# Power.net
KiCad netlist of a schematic drawn in Altium Designer
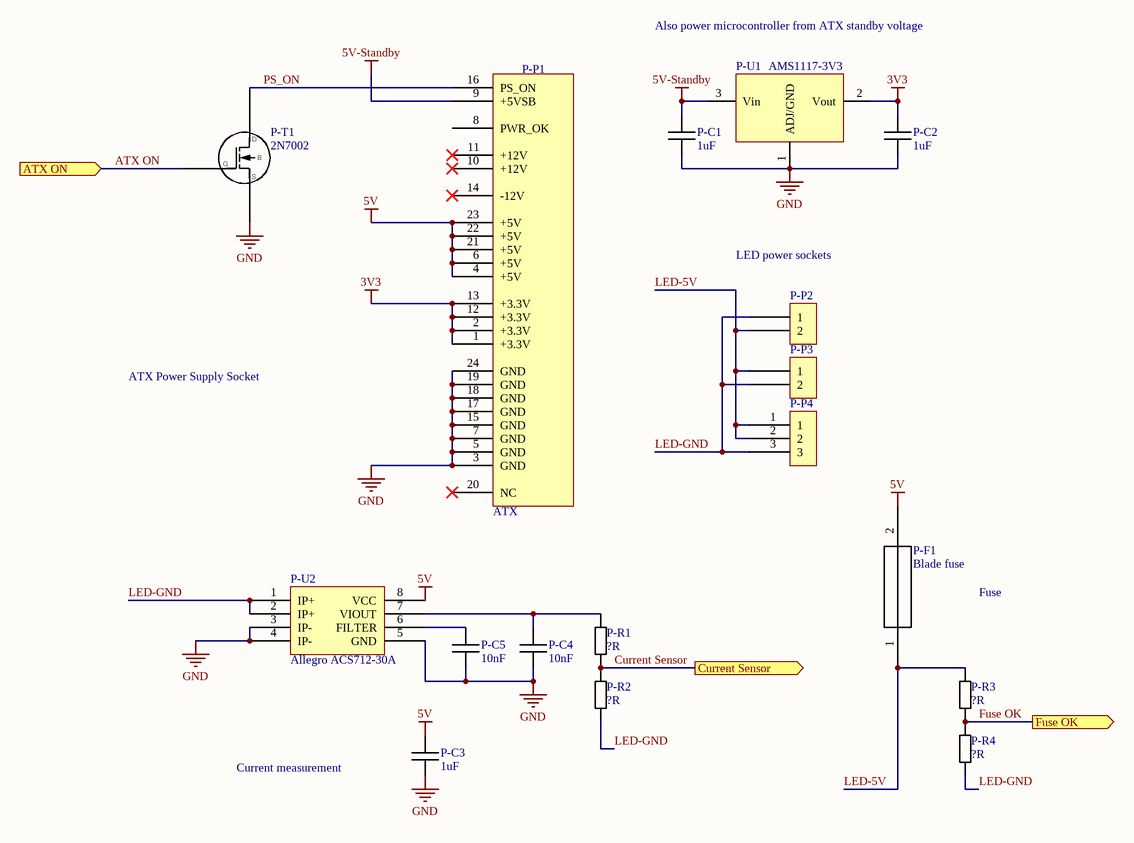
[diagram p0: Power.SchDoc]

(export (version "E")
  (design (tool "Eeschema 10.0.6"))
  (components
    (comp (ref "P-C1")
      (value "1uF")
      (footprint "C 0805 / 2012")
      (libsource (lib "Standard") (part "Capacitor"))
    )
    (comp (ref "P-C2")
      (value "1uF")
      (footprint "C 0805 / 2012")
      (libsource (lib "Standard") (part "Capacitor"))
    )
    (comp (ref "P-C3")
      (value "1uF")
      (footprint "C 0805 / 2012")
      (libsource (lib "Standard") (part "Capacitor"))
    )
    (comp (ref "P-C4")
      (value "10nF")
      (footprint "R 0805 / 2012 wide")
      (libsource (lib "Standard") (part "Capacitor"))
    )
    (comp (ref "P-C5")
      (value "10nF")
      (footprint "C 0805 / 2012")
      (libsource (lib "Standard") (part "Capacitor"))
    )
    (comp (ref "P-F1")
      (value "Blade fuse")
      (footprint "Blade fuse receptacle")
      (libsource (lib "Standard") (part "Fuse"))
    )
    (comp (ref "P-P1") (value "ATX") (footprint "ATX") (libsource (lib "Connectors") (part "ATX sorted")))
    (comp (ref "P-P2")
      (value "Header 2x1")
      (footprint "Screw terminal 2 pin RM 5mm")
      (libsource (lib "Headers") (part "Header 2x1"))
    )
    (comp (ref "P-P3")
      (value "Header 2x1")
      (footprint "Screw terminal 2 pin RM 5mm")
      (libsource (lib "Headers") (part "Header 2x1"))
    )
    (comp (ref "P-P4")
      (value "Header 1x3")
      (footprint "Screw terminal 3 pin RM 7.62mm")
      (libsource (lib "Headers") (part "Header 1x3"))
    )
    (comp (ref "P-R1")
      (value "?R")
      (footprint "R 0805 / 2012")
      (libsource (lib "Standard") (part "Resistor"))
    )
    (comp (ref "P-R2")
      (value "?R")
      (footprint "R 0805 / 2012")
      (libsource (lib "Standard") (part "Resistor"))
    )
    (comp (ref "P-R3")
      (value "?R")
      (footprint "R 0805 / 2012")
      (libsource (lib "Standard") (part "Resistor"))
    )
    (comp (ref "P-R4")
      (value "?R")
      (footprint "R 0805 / 2012")
      (libsource (lib "Standard") (part "Resistor"))
    )
    (comp (ref "P-T1")
      (value "2N7002")
      (footprint "SOT-23-3")
      (description "N-FET")
      (libsource (lib "ICs") (part "2N7002"))
    )
    (comp (ref "P-U1")
      (value "AMS1117-3V3")
      (footprint "SOT-223-3")
      (description "LDO 3.3V/5V/12V")
      (libsource (lib "ICs") (part "AMS1117"))
    )
    (comp (ref "P-U2")
      (value "Allegro ACS712-30A")
      (footprint "SOIC-8")
      (description "Analog current sensor")
      (libsource (lib "ICs") (part "Allegro ACS712"))
    )
  )
  (nets
    (net (code "1") (name "/ATX ON") (class "Default")
      (node (ref "P-T1") (pin "1") (pinfunction "1_1") (pintype "passive"))
    )
    (net (code "2") (name "/Current Sensor") (class "Default")
      (node (ref "P-R1") (pin "1") (pinfunction "1_1") (pintype "passive"))
      (node (ref "P-R2") (pin "2") (pinfunction "2_2") (pintype "passive"))
    )
    (net (code "3") (name "/Fuse OK") (class "Default")
      (node (ref "P-R3") (pin "1") (pinfunction "1_1") (pintype "passive"))
      (node (ref "P-R4") (pin "2") (pinfunction "2_2") (pintype "passive"))
    )
    (net (code "4") (name "/LED-5V") (class "Default")
      (node (ref "P-F1") (pin "1") (pinfunction "1_1") (pintype "passive"))
      (node (ref "P-P2") (pin "2") (pinfunction "2_2") (pintype "passive"))
      (node (ref "P-P3") (pin "1") (pinfunction "1_1") (pintype "passive"))
      (node (ref "P-P4") (pin "1") (pinfunction "1_1") (pintype "passive"))
      (node (ref "P-P4") (pin "2") (pinfunction "2_2") (pintype "passive"))
      (node (ref "P-R3") (pin "2") (pinfunction "2_2") (pintype "passive"))
    )
    (net (code "5") (name "/LED-GND") (class "Default")
      (node (ref "P-P2") (pin "1") (pinfunction "1_1") (pintype "passive"))
      (node (ref "P-P3") (pin "2") (pinfunction "2_2") (pintype "passive"))
      (node (ref "P-P4") (pin "3") (pinfunction "3_3") (pintype "passive"))
      (node (ref "P-R2") (pin "1") (pinfunction "1_1") (pintype "passive"))
      (node (ref "P-R4") (pin "1") (pinfunction "1_1") (pintype "passive"))
      (node (ref "P-U2") (pin "1") (pinfunction "IP+_1") (pintype "passive"))
      (node (ref "P-U2") (pin "2") (pinfunction "IP+_2") (pintype "passive"))
    )
    (net (code "6") (name "/PS_ON") (class "Default")
      (node (ref "P-P1") (pin "16") (pinfunction "PS_ON_16") (pintype "passive"))
      (node (ref "P-T1") (pin "3") (pinfunction "3_3") (pintype "passive"))
    )
    (net (code "7") (name "3V3") (class "Default")
      (node (ref "P-C2") (pin "1") (pinfunction "1_1") (pintype "passive"))
      (node (ref "P-P1") (pin "1") (pinfunction "+3.3V_1") (pintype "passive"))
      (node (ref "P-P1") (pin "12") (pinfunction "+3.3V_12") (pintype "passive"))
      (node (ref "P-P1") (pin "13") (pinfunction "+3.3V_13") (pintype "passive"))
      (node (ref "P-P1") (pin "2") (pinfunction "+3.3V_2") (pintype "passive"))
      (node (ref "P-U1") (pin "2") (pinfunction "Vout_2") (pintype "passive"))
    )
    (net (code "8") (name "5V") (class "Default")
      (node (ref "P-C3") (pin "1") (pinfunction "1_1") (pintype "passive"))
      (node (ref "P-F1") (pin "2") (pinfunction "2_2") (pintype "passive"))
      (node (ref "P-P1") (pin "21") (pinfunction "+5V_21") (pintype "passive"))
      (node (ref "P-P1") (pin "22") (pinfunction "+5V_22") (pintype "passive"))
      (node (ref "P-P1") (pin "23") (pinfunction "+5V_23") (pintype "passive"))
      (node (ref "P-P1") (pin "4") (pinfunction "+5V_4") (pintype "passive"))
      (node (ref "P-P1") (pin "6") (pinfunction "+5V_6") (pintype "passive"))
      (node (ref "P-U2") (pin "8") (pinfunction "VCC_8") (pintype "passive"))
    )
    (net (code "9") (name "5V-Standby") (class "Default")
      (node (ref "P-C1") (pin "1") (pinfunction "1_1") (pintype "passive"))
      (node (ref "P-P1") (pin "9") (pinfunction "+5VSB_9") (pintype "passive"))
      (node (ref "P-U1") (pin "3") (pinfunction "Vin_3") (pintype "passive"))
    )
    (net (code "10") (name "GND") (class "Default")
      (node (ref "P-C1") (pin "2") (pinfunction "1_2") (pintype "passive"))
      (node (ref "P-C2") (pin "2") (pinfunction "1_2") (pintype "passive"))
      (node (ref "P-C3") (pin "2") (pinfunction "1_2") (pintype "passive"))
      (node (ref "P-C4") (pin "2") (pinfunction "1_2") (pintype "passive"))
      (node (ref "P-C5") (pin "2") (pinfunction "1_2") (pintype "passive"))
      (node (ref "P-P1") (pin "15") (pinfunction "GND_15") (pintype "passive"))
      (node (ref "P-P1") (pin "17") (pinfunction "GND_17") (pintype "passive"))
      (node (ref "P-P1") (pin "18") (pinfunction "GND_18") (pintype "passive"))
      (node (ref "P-P1") (pin "19") (pinfunction "GND_19") (pintype "passive"))
      (node (ref "P-P1") (pin "24") (pinfunction "GND_24") (pintype "passive"))
      (node (ref "P-P1") (pin "3") (pinfunction "GND_3") (pintype "passive"))
      (node (ref "P-P1") (pin "5") (pinfunction "GND_5") (pintype "passive"))
      (node (ref "P-P1") (pin "7") (pinfunction "GND_7") (pintype "passive"))
      (node (ref "P-T1") (pin "2") (pinfunction "2_2") (pintype "passive"))
      (node (ref "P-U1") (pin "1") (pinfunction "ADJ/GND_1") (pintype "passive"))
      (node (ref "P-U2") (pin "3") (pinfunction "IP-_3") (pintype "passive"))
      (node (ref "P-U2") (pin "4") (pinfunction "IP-_4") (pintype "passive"))
      (node (ref "P-U2") (pin "5") (pinfunction "GND_5") (pintype "passive"))
    )
    (net (code "11") (name "Net-(P-U2-FILTER)") (class "Default")
      (node (ref "P-C5") (pin "1") (pinfunction "1_1") (pintype "passive"))
      (node (ref "P-U2") (pin "6") (pinfunction "FILTER_6") (pintype "passive"))
    )
    (net (code "12") (name "Net-(P-U2-VIOUT)") (class "Default")
      (node (ref "P-C4") (pin "1") (pinfunction "1_1") (pintype "passive"))
      (node (ref "P-R1") (pin "2") (pinfunction "2_2") (pintype "passive"))
      (node (ref "P-U2") (pin "7") (pinfunction "VIOUT_7") (pintype "passive"))
    )
    (net (code "13") (name "unconnected-(P-P1-+12V-Pad10)") (class "Default")
      (node (ref "P-P1") (pin "10") (pinfunction "+12V_10") (pintype "passive+no_connect"))
    )
    (net (code "14") (name "unconnected-(P-P1-+12V-Pad11)") (class "Default")
      (node (ref "P-P1") (pin "11") (pinfunction "+12V_11") (pintype "passive+no_connect"))
    )
    (net (code "15") (name "unconnected-(P-P1--12V-Pad14)") (class "Default")
      (node (ref "P-P1") (pin "14") (pinfunction "-12V_14") (pintype "passive+no_connect"))
    )
    (net (code "16") (name "unconnected-(P-P1-NC-Pad20)") (class "Default")
      (node (ref "P-P1") (pin "20") (pinfunction "NC_20") (pintype "passive+no_connect"))
    )
    (net (code "17") (name "unconnected-(P-P1-PWR_OK-Pad8)") (class "Default")
      (node (ref "P-P1") (pin "8") (pinfunction "PWR_OK_8") (pintype "passive"))
    )
  )
)
